# SD_CARD.net
KiCad netlist of a schematic drawn in Altium Designer
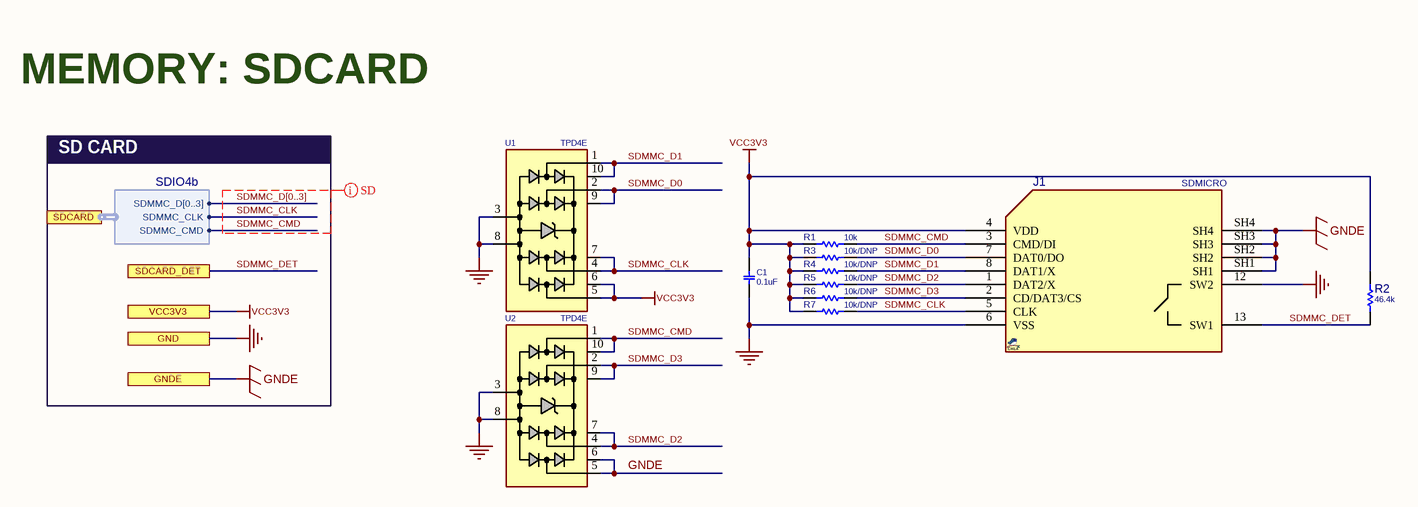
[diagram p0: SD_CARD.SchDoc]

(export (version "E")
  (design (tool "Eeschema 10.0.6"))
  (components
    (comp (ref "C1")
      (value "0.1uF")
      (footprint "C0402")
      (description "CAP, MLCC")
      (fields (field (name "MANF_P#") "GRM155R61E104") (field (name "MANF") "Murata"))
      (libsource (lib "mlcc_smd_passive") (part "CAP_SMD_MLCC_100n50TDK"))
    )
    (comp (ref "J1")
      (value "SDMICRO")
      (footprint "SDMICRO_MOLEX104031")
      (description "CONN MICRO SD R/A PUSHin-PULLout SMD")
      (fields (field (name "MANF") "Molex") (field (name "MANF_P#") "104031-0811"))
      (libsource (lib "socket_card") (part "SOCKET_SDMICRO_MOLEX104031"))
    )
    (comp (ref "R1")
      (value "10k")
      (footprint "R0402")
      (description "RESISTOR, SMD")
      (libsource (lib "passive_res_smd") (part "RES_SMD"))
    )
    (comp (ref "R2")
      (value "46.4k")
      (footprint "R0402")
      (description "RESISTOR, SMD")
      (libsource (lib "passive_res_smd") (part "RES_SMD"))
    )
    (comp (ref "R3")
      (value "10k/DNP")
      (footprint "R0402")
      (description "RESISTOR, SMD")
      (libsource (lib "passive_res_smd") (part "RES_SMD"))
    )
    (comp (ref "R4")
      (value "10k/DNP")
      (footprint "R0402")
      (description "RESISTOR, SMD")
      (libsource (lib "passive_res_smd") (part "RES_SMD"))
    )
    (comp (ref "R5")
      (value "10k/DNP")
      (footprint "R0402")
      (description "RESISTOR, SMD")
      (libsource (lib "passive_res_smd") (part "RES_SMD"))
    )
    (comp (ref "R6")
      (value "10k/DNP")
      (footprint "R0402")
      (description "RESISTOR, SMD")
      (libsource (lib "passive_res_smd") (part "RES_SMD"))
    )
    (comp (ref "R7")
      (value "10k/DNP")
      (footprint "R0402")
      (description "RESISTOR, SMD")
      (libsource (lib "passive_res_smd") (part "RES_SMD"))
    )
    (comp (ref "U1")
      (value "TPD4E")
      (footprint "SON50_10_2510")
      (description "TVS, ESD PROTECT, 4CH,")
      (fields (field (name "MANF_P#") "TPD4E05U06DQA") (field (name "MANF") "Texas Instruments"))
      (libsource (lib "protect_tvs_esd_fuse") (part "TVS_X4_TPD4E05U06"))
    )
    (comp (ref "U2")
      (value "TPD4E")
      (footprint "SON50_10_2510")
      (description "TVS, ESD PROTECT, 4CH,")
      (fields (field (name "MANF_P#") "TPD4E05U06DQA") (field (name "MANF") "Texas Instruments"))
      (libsource (lib "protect_tvs_esd_fuse") (part "TVS_X4_TPD4E05U06"))
    )
  )
  (nets
    (net (code "2") (name "/SDMMC_CLK") (class "Default")
      (node (ref "J1") (pin "5") (pinfunction "CLK_5") (pintype "passive"))
      (node (ref "R7") (pin "2") (pinfunction "2_2") (pintype "passive"))
      (node (ref "U1") (pin "4") (pinfunction "4_4") (pintype "passive"))
      (node (ref "U1") (pin "7") (pinfunction "7_7") (pintype "passive"))
    )
    (net (code "3") (name "/SDMMC_CMD") (class "Default")
      (node (ref "J1") (pin "3") (pinfunction "CMD/DI_3") (pintype "passive"))
      (node (ref "R1") (pin "2") (pinfunction "2_2") (pintype "passive"))
      (node (ref "U2") (pin "1") (pinfunction "1_1") (pintype "passive"))
      (node (ref "U2") (pin "10") (pinfunction "10_10") (pintype "passive"))
    )
    (net (code "4") (name "/SDMMC_D0") (class "Default")
      (node (ref "J1") (pin "7") (pinfunction "DAT0/DO_7") (pintype "passive"))
      (node (ref "R3") (pin "2") (pinfunction "2_2") (pintype "passive"))
      (node (ref "U1") (pin "2") (pinfunction "2_2") (pintype "passive"))
      (node (ref "U1") (pin "9") (pinfunction "9_9") (pintype "passive"))
    )
    (net (code "5") (name "/SDMMC_D1") (class "Default")
      (node (ref "J1") (pin "8") (pinfunction "DAT1/X_8") (pintype "passive"))
      (node (ref "R4") (pin "2") (pinfunction "2_2") (pintype "passive"))
      (node (ref "U1") (pin "1") (pinfunction "1_1") (pintype "passive"))
      (node (ref "U1") (pin "10") (pinfunction "10_10") (pintype "passive"))
    )
    (net (code "6") (name "/SDMMC_D2") (class "Default")
      (node (ref "J1") (pin "1") (pinfunction "DAT2/X_1") (pintype "passive"))
      (node (ref "R5") (pin "2") (pinfunction "2_2") (pintype "passive"))
      (node (ref "U2") (pin "4") (pinfunction "4_4") (pintype "passive"))
      (node (ref "U2") (pin "7") (pinfunction "7_7") (pintype "passive"))
    )
    (net (code "7") (name "/SDMMC_D3") (class "Default")
      (node (ref "J1") (pin "2") (pinfunction "CD/DAT3/CS_2") (pintype "passive"))
      (node (ref "R6") (pin "2") (pinfunction "2_2") (pintype "passive"))
      (node (ref "U2") (pin "2") (pinfunction "2_2") (pintype "passive"))
      (node (ref "U2") (pin "9") (pinfunction "9_9") (pintype "passive"))
    )
    (net (code "8") (name "/SDMMC_DET") (class "Default")
      (node (ref "J1") (pin "13") (pinfunction "SW1_13") (pintype "passive"))
      (node (ref "R2") (pin "1") (pinfunction "1_1") (pintype "passive"))
    )
    (net (code "11") (name "GND") (class "Default")
      (node (ref "C1") (pin "2") (pinfunction "2_2") (pintype "passive"))
      (node (ref "J1") (pin "12") (pinfunction "SW2_12") (pintype "passive"))
      (node (ref "J1") (pin "6") (pinfunction "VSS_6") (pintype "passive"))
      (node (ref "U1") (pin "3") (pinfunction "3_3") (pintype "passive"))
      (node (ref "U1") (pin "8") (pinfunction "8_8") (pintype "passive"))
      (node (ref "U2") (pin "3") (pinfunction "3_3") (pintype "passive"))
      (node (ref "U2") (pin "8") (pinfunction "8_8") (pintype "passive"))
    )
    (net (code "12") (name "GNDE") (class "Default")
      (node (ref "J1") (pin "SH1") (pinfunction "SH1_SH1") (pintype "passive"))
      (node (ref "J1") (pin "SH2") (pinfunction "SH2_SH2") (pintype "passive"))
      (node (ref "J1") (pin "SH3") (pinfunction "SH3_SH3") (pintype "passive"))
      (node (ref "J1") (pin "SH4") (pinfunction "SH4_SH4") (pintype "passive"))
      (node (ref "U2") (pin "5") (pinfunction "5_5") (pintype "passive"))
      (node (ref "U2") (pin "6") (pinfunction "6_6") (pintype "passive"))
    )
    (net (code "13") (name "VCC3V3") (class "Default")
      (node (ref "C1") (pin "1") (pinfunction "1_1") (pintype "passive"))
      (node (ref "J1") (pin "4") (pinfunction "VDD_4") (pintype "passive"))
      (node (ref "R1") (pin "1") (pinfunction "1_1") (pintype "passive"))
      (node (ref "R2") (pin "2") (pinfunction "2_2") (pintype "passive"))
      (node (ref "R3") (pin "1") (pinfunction "1_1") (pintype "passive"))
      (node (ref "R4") (pin "1") (pinfunction "1_1") (pintype "passive"))
      (node (ref "R5") (pin "1") (pinfunction "1_1") (pintype "passive"))
      (node (ref "R6") (pin "1") (pinfunction "1_1") (pintype "passive"))
      (node (ref "R7") (pin "1") (pinfunction "1_1") (pintype "passive"))
      (node (ref "U1") (pin "5") (pinfunction "5_5") (pintype "passive"))
      (node (ref "U1") (pin "6") (pinfunction "6_6") (pintype "passive"))
    )
  )
)
